# 1_AMM592.net
KiCad netlist of a schematic drawn in Altium Designer
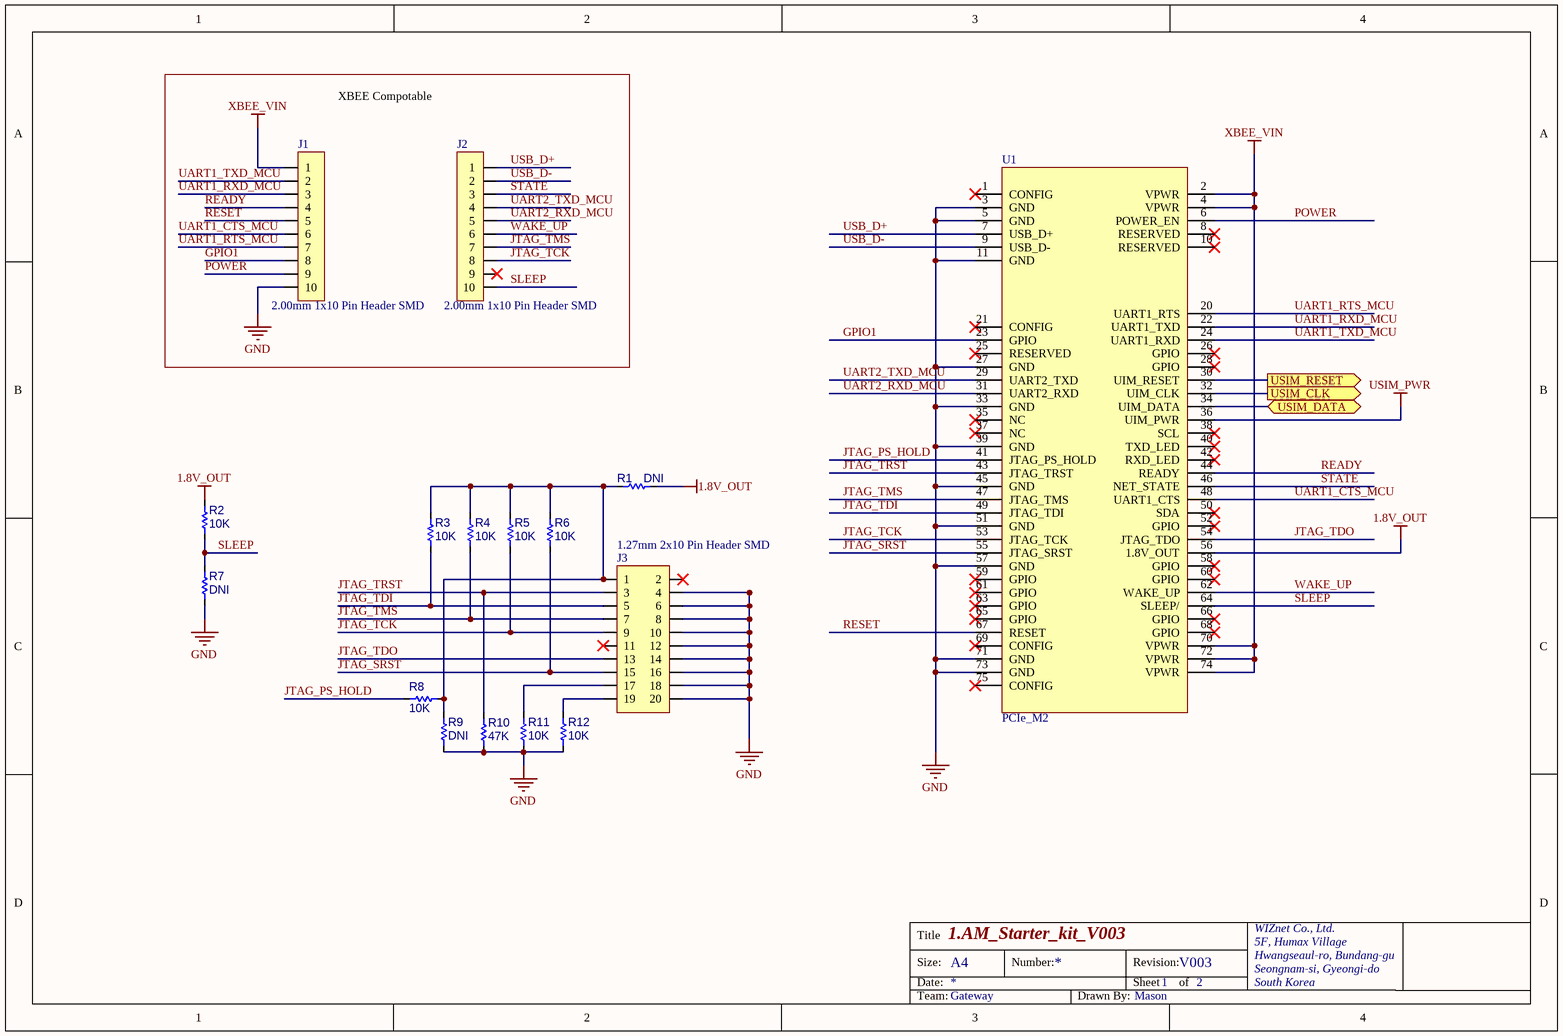
[diagram p0: 1.AMM592.SchDoc]

(export (version "E")
  (design (tool "Eeschema 10.0.6"))
  (components
    (comp (ref "J1")
      (value "2.00mm 1x10 Pin Header SMD")
      (footprint "IDC(SMD)-1X10(2MM)")
      (libsource (lib "") (part "2.00mm 1x10 Pin Header SMD_1"))
    )
    (comp (ref "J2")
      (value "2.00mm 1x10 Pin Header SMD")
      (footprint "IDC(SMD)-1X10(2MM)")
      (libsource (lib "Scott_lib") (part "2.00mm 1x10 Pin Header SMD"))
    )
    (comp (ref "J3")
      (value "1.27mm 2x10 Pin Header SMD")
      (footprint "IDC(SMD)-2X10(1.27MM)")
      (libsource (lib "Scott_lib") (part "1.27mm 2x10 Pin Header SMD"))
    )
    (comp (ref "R1")
      (value "DNI")
      (footprint "RES-0402")
      (description "RES-0402")
      (libsource (lib "Scott_lib") (part "RES-0402"))
    )
    (comp (ref "R2")
      (value "10K")
      (footprint "RES-0402")
      (description "RES-0402")
      (libsource (lib "Scott_lib") (part "RES-0402"))
    )
    (comp (ref "R3")
      (value "10K")
      (footprint "RES-0402")
      (description "RES-0402")
      (libsource (lib "Scott_lib") (part "RES-0402"))
    )
    (comp (ref "R4")
      (value "10K")
      (footprint "RES-0402")
      (description "RES-0402")
      (libsource (lib "Scott_lib") (part "RES-0402"))
    )
    (comp (ref "R5")
      (value "10K")
      (footprint "RES-0402")
      (description "RES-0402")
      (libsource (lib "Scott_lib") (part "RES-0402"))
    )
    (comp (ref "R6")
      (value "10K")
      (footprint "RES-0402")
      (description "RES-0402")
      (libsource (lib "Scott_lib") (part "RES-0402"))
    )
    (comp (ref "R7")
      (value "DNI")
      (footprint "RES-0402")
      (description "RES-0402")
      (libsource (lib "Scott_lib") (part "RES-0402"))
    )
    (comp (ref "R8")
      (value "10K")
      (footprint "RES-0402")
      (description "RES-0402")
      (libsource (lib "Scott_lib") (part "RES-0402"))
    )
    (comp (ref "R9")
      (value "DNI")
      (footprint "RES-0402")
      (description "RES-0402")
      (libsource (lib "Scott_lib") (part "RES-0402"))
    )
    (comp (ref "R10")
      (value "47K")
      (footprint "RES-0402")
      (description "RES-0402")
      (libsource (lib "Scott_lib") (part "RES-0402"))
    )
    (comp (ref "R11")
      (value "10K")
      (footprint "RES-0402")
      (description "RES-0402")
      (libsource (lib "Scott_lib") (part "RES-0402"))
    )
    (comp (ref "R12")
      (value "10K")
      (footprint "RES-0402")
      (description "RES-0402")
      (libsource (lib "Scott_lib") (part "RES-0402"))
    )
    (comp (ref "U1")
      (value "PCIe_M2")
      (footprint "PCIe_M2")
      (libsource (lib "AM_Starter_kit") (part "PCIe-M2"))
    )
  )
  (nets
    (net (code "1") (name "/GPIO1") (class "Default")
      (node (ref "J1") (pin "8") (pinfunction "8_8") (pintype "passive"))
      (node (ref "U1") (pin "23") (pinfunction "GPIO_23") (pintype "passive"))
    )
    (net (code "2") (name "/JTAG_PS_HOLD") (class "Default")
      (node (ref "R8") (pin "2") (pinfunction "2_2") (pintype "passive"))
      (node (ref "U1") (pin "41") (pinfunction "JTAG_PS_HOLD_41") (pintype "passive"))
    )
    (net (code "3") (name "/JTAG_SRST") (class "Default")
      (node (ref "J3") (pin "15") (pinfunction "15_15") (pintype "passive"))
      (node (ref "R6") (pin "1") (pinfunction "1_1") (pintype "passive"))
      (node (ref "U1") (pin "55") (pinfunction "JTAG_SRST_55") (pintype "passive"))
    )
    (net (code "4") (name "/JTAG_TCK") (class "Default")
      (node (ref "J2") (pin "8") (pinfunction "8_8") (pintype "passive"))
      (node (ref "J3") (pin "9") (pinfunction "9_9") (pintype "passive"))
      (node (ref "R5") (pin "1") (pinfunction "1_1") (pintype "passive"))
      (node (ref "U1") (pin "53") (pinfunction "JTAG_TCK_53") (pintype "passive"))
    )
    (net (code "5") (name "/JTAG_TDI") (class "Default")
      (node (ref "J3") (pin "5") (pinfunction "5_5") (pintype "passive"))
      (node (ref "R3") (pin "1") (pinfunction "1_1") (pintype "passive"))
      (node (ref "U1") (pin "49") (pinfunction "JTAG_TDI_49") (pintype "passive"))
    )
    (net (code "6") (name "/JTAG_TDO") (class "Default")
      (node (ref "J3") (pin "13") (pinfunction "13_13") (pintype "passive"))
      (node (ref "U1") (pin "54") (pinfunction "JTAG_TDO_54") (pintype "passive"))
    )
    (net (code "7") (name "/JTAG_TMS") (class "Default")
      (node (ref "J2") (pin "7") (pinfunction "7_7") (pintype "passive"))
      (node (ref "J3") (pin "7") (pinfunction "7_7") (pintype "passive"))
      (node (ref "R4") (pin "1") (pinfunction "1_1") (pintype "passive"))
      (node (ref "U1") (pin "47") (pinfunction "JTAG_TMS_47") (pintype "passive"))
    )
    (net (code "8") (name "/JTAG_TRST") (class "Default")
      (node (ref "J3") (pin "3") (pinfunction "3_3") (pintype "passive"))
      (node (ref "R10") (pin "2") (pinfunction "2_2") (pintype "passive"))
      (node (ref "U1") (pin "43") (pinfunction "JTAG_TRST_43") (pintype "passive"))
    )
    (net (code "9") (name "/POWER") (class "Default")
      (node (ref "J1") (pin "9") (pinfunction "9_9") (pintype "passive"))
      (node (ref "U1") (pin "6") (pinfunction "POWER_EN_6") (pintype "passive"))
    )
    (net (code "10") (name "/READY") (class "Default")
      (node (ref "J1") (pin "4") (pinfunction "4_4") (pintype "passive"))
      (node (ref "U1") (pin "44") (pinfunction "READY_44") (pintype "passive"))
    )
    (net (code "11") (name "/RESET") (class "Default")
      (node (ref "J1") (pin "5") (pinfunction "5_5") (pintype "passive"))
      (node (ref "U1") (pin "67") (pinfunction "RESET_67") (pintype "passive"))
    )
    (net (code "12") (name "/SLEEP") (class "Default")
      (node (ref "J2") (pin "10") (pinfunction "10_10") (pintype "passive"))
      (node (ref "R2") (pin "1") (pinfunction "1_1") (pintype "passive"))
      (node (ref "R7") (pin "2") (pinfunction "2_2") (pintype "passive"))
      (node (ref "U1") (pin "64") (pinfunction "SLEEP/_64") (pintype "passive"))
    )
    (net (code "13") (name "/STATE") (class "Default")
      (node (ref "J2") (pin "3") (pinfunction "3_3") (pintype "passive"))
      (node (ref "U1") (pin "46") (pinfunction "NET_STATE_46") (pintype "passive"))
    )
    (net (code "14") (name "/UART1_CTS_MCU") (class "Default")
      (node (ref "J1") (pin "6") (pinfunction "6_6") (pintype "passive"))
      (node (ref "U1") (pin "48") (pinfunction "UART1_CTS_48") (pintype "passive"))
    )
    (net (code "15") (name "/UART1_RTS_MCU") (class "Default")
      (node (ref "J1") (pin "7") (pinfunction "7_7") (pintype "passive"))
      (node (ref "U1") (pin "20") (pinfunction "UART1_RTS_20") (pintype "passive"))
    )
    (net (code "16") (name "/UART1_RXD_MCU") (class "Default")
      (node (ref "J1") (pin "3") (pinfunction "3_3") (pintype "passive"))
      (node (ref "U1") (pin "22") (pinfunction "UART1_TXD_22") (pintype "passive"))
    )
    (net (code "17") (name "/UART1_TXD_MCU") (class "Default")
      (node (ref "J1") (pin "2") (pinfunction "2_2") (pintype "passive"))
      (node (ref "U1") (pin "24") (pinfunction "UART1_RXD_24") (pintype "passive"))
    )
    (net (code "18") (name "/UART2_RXD_MCU") (class "Default")
      (node (ref "J2") (pin "5") (pinfunction "5_5") (pintype "passive"))
      (node (ref "U1") (pin "31") (pinfunction "UART2_RXD_31") (pintype "passive"))
    )
    (net (code "19") (name "/UART2_TXD_MCU") (class "Default")
      (node (ref "J2") (pin "4") (pinfunction "4_4") (pintype "passive"))
      (node (ref "U1") (pin "29") (pinfunction "UART2_TXD_29") (pintype "passive"))
    )
    (net (code "20") (name "/USB_D+") (class "Default")
      (node (ref "J2") (pin "1") (pinfunction "1_1") (pintype "passive"))
      (node (ref "U1") (pin "7") (pinfunction "USB_D+_7") (pintype "passive"))
    )
    (net (code "21") (name "/USB_D-") (class "Default")
      (node (ref "J2") (pin "2") (pinfunction "2_2") (pintype "passive"))
      (node (ref "U1") (pin "9") (pinfunction "USB_D-_9") (pintype "passive"))
    )
    (net (code "22") (name "/USIM_CLK") (class "Default")
      (node (ref "U1") (pin "32") (pinfunction "UIM_CLK_32") (pintype "passive"))
    )
    (net (code "23") (name "/USIM_DATA") (class "Default")
      (node (ref "U1") (pin "34") (pinfunction "UIM_DATA_34") (pintype "passive"))
    )
    (net (code "24") (name "/USIM_RESET") (class "Default")
      (node (ref "U1") (pin "30") (pinfunction "UIM_RESET_30") (pintype "passive"))
    )
    (net (code "25") (name "/WAKE_UP") (class "Default")
      (node (ref "J2") (pin "6") (pinfunction "6_6") (pintype "passive"))
      (node (ref "U1") (pin "62") (pinfunction "WAKE_UP_62") (pintype "passive"))
    )
    (net (code "26") (name "1.8V_OUT") (class "Default")
      (node (ref "R1") (pin "1") (pinfunction "1_1") (pintype "passive"))
      (node (ref "R2") (pin "2") (pinfunction "2_2") (pintype "passive"))
      (node (ref "U1") (pin "56") (pinfunction "1.8V_OUT_56") (pintype "passive"))
    )
    (net (code "27") (name "GND") (class "Default")
      (node (ref "J1") (pin "10") (pinfunction "10_10") (pintype "passive"))
      (node (ref "J3") (pin "10") (pinfunction "10_10") (pintype "passive"))
      (node (ref "J3") (pin "12") (pinfunction "12_12") (pintype "passive"))
      (node (ref "J3") (pin "14") (pinfunction "14_14") (pintype "passive"))
      (node (ref "J3") (pin "16") (pinfunction "16_16") (pintype "passive"))
      (node (ref "J3") (pin "18") (pinfunction "18_18") (pintype "passive"))
      (node (ref "J3") (pin "20") (pinfunction "20_20") (pintype "passive"))
      (node (ref "J3") (pin "4") (pinfunction "4_4") (pintype "passive"))
      (node (ref "J3") (pin "6") (pinfunction "6_6") (pintype "passive"))
      (node (ref "J3") (pin "8") (pinfunction "8_8") (pintype "passive"))
      (node (ref "R10") (pin "1") (pinfunction "1_1") (pintype "passive"))
      (node (ref "R11") (pin "1") (pinfunction "1_1") (pintype "passive"))
      (node (ref "R12") (pin "1") (pinfunction "1_1") (pintype "passive"))
      (node (ref "R7") (pin "1") (pinfunction "1_1") (pintype "passive"))
      (node (ref "R9") (pin "1") (pinfunction "1_1") (pintype "passive"))
      (node (ref "U1") (pin "11") (pinfunction "GND_11") (pintype "passive"))
      (node (ref "U1") (pin "27") (pinfunction "GND_27") (pintype "passive"))
      (node (ref "U1") (pin "3") (pinfunction "GND_3") (pintype "passive"))
      (node (ref "U1") (pin "33") (pinfunction "GND_33") (pintype "passive"))
      (node (ref "U1") (pin "39") (pinfunction "GND_39") (pintype "passive"))
      (node (ref "U1") (pin "45") (pinfunction "GND_45") (pintype "passive"))
      (node (ref "U1") (pin "5") (pinfunction "GND_5") (pintype "passive"))
      (node (ref "U1") (pin "51") (pinfunction "GND_51") (pintype "passive"))
      (node (ref "U1") (pin "57") (pinfunction "GND_57") (pintype "passive"))
      (node (ref "U1") (pin "71") (pinfunction "GND_71") (pintype "passive"))
      (node (ref "U1") (pin "73") (pinfunction "GND_73") (pintype "passive"))
    )
    (net (code "28") (name "Net-(J3-Pad1)") (class "Default")
      (node (ref "J3") (pin "1") (pinfunction "1_1") (pintype "passive"))
      (node (ref "R1") (pin "2") (pinfunction "2_2") (pintype "passive"))
      (node (ref "R3") (pin "2") (pinfunction "2_2") (pintype "passive"))
      (node (ref "R4") (pin "2") (pinfunction "2_2") (pintype "passive"))
      (node (ref "R5") (pin "2") (pinfunction "2_2") (pintype "passive"))
      (node (ref "R6") (pin "2") (pinfunction "2_2") (pintype "passive"))
      (node (ref "R8") (pin "1") (pinfunction "1_1") (pintype "passive"))
      (node (ref "R9") (pin "2") (pinfunction "2_2") (pintype "passive"))
    )
    (net (code "29") (name "Net-(J3-Pad17)") (class "Default")
      (node (ref "J3") (pin "17") (pinfunction "17_17") (pintype "passive"))
      (node (ref "R11") (pin "2") (pinfunction "2_2") (pintype "passive"))
    )
    (net (code "30") (name "Net-(J3-Pad19)") (class "Default")
      (node (ref "J3") (pin "19") (pinfunction "19_19") (pintype "passive"))
      (node (ref "R12") (pin "2") (pinfunction "2_2") (pintype "passive"))
    )
    (net (code "31") (name "USIM_PWR") (class "Default")
      (node (ref "U1") (pin "36") (pinfunction "UIM_PWR_36") (pintype "passive"))
    )
    (net (code "32") (name "XBEE_VIN") (class "Default")
      (node (ref "J1") (pin "1") (pinfunction "1_1") (pintype "passive"))
      (node (ref "U1") (pin "2") (pinfunction "VPWR_2") (pintype "passive"))
      (node (ref "U1") (pin "4") (pinfunction "VPWR_4") (pintype "passive"))
      (node (ref "U1") (pin "70") (pinfunction "VPWR_70") (pintype "passive"))
      (node (ref "U1") (pin "72") (pinfunction "VPWR_72") (pintype "passive"))
      (node (ref "U1") (pin "74") (pinfunction "VPWR_74") (pintype "passive"))
    )
    (net (code "33") (name "unconnected-(J2-Pad9)") (class "Default")
      (node (ref "J2") (pin "9") (pinfunction "9_9") (pintype "passive+no_connect"))
    )
    (net (code "34") (name "unconnected-(J3-Pad2)") (class "Default")
      (node (ref "J3") (pin "2") (pinfunction "2_2") (pintype "passive+no_connect"))
    )
    (net (code "35") (name "unconnected-(J3-Pad11)") (class "Default")
      (node (ref "J3") (pin "11") (pinfunction "11_11") (pintype "passive+no_connect"))
    )
    (net (code "36") (name "unconnected-(U1-CONFIG-Pad1)") (class "Default")
      (node (ref "U1") (pin "1") (pinfunction "CONFIG_1") (pintype "passive+no_connect"))
    )
    (net (code "37") (name "unconnected-(U1-CONFIG-Pad21)") (class "Default")
      (node (ref "U1") (pin "21") (pinfunction "CONFIG_21") (pintype "passive+no_connect"))
    )
    (net (code "38") (name "unconnected-(U1-CONFIG-Pad69)") (class "Default")
      (node (ref "U1") (pin "69") (pinfunction "CONFIG_69") (pintype "passive+no_connect"))
    )
    (net (code "39") (name "unconnected-(U1-CONFIG-Pad75)") (class "Default")
      (node (ref "U1") (pin "75") (pinfunction "CONFIG_75") (pintype "passive+no_connect"))
    )
    (net (code "40") (name "unconnected-(U1-GPIO-Pad26)") (class "Default")
      (node (ref "U1") (pin "26") (pinfunction "GPIO_26") (pintype "passive+no_connect"))
    )
    (net (code "41") (name "unconnected-(U1-GPIO-Pad28)") (class "Default")
      (node (ref "U1") (pin "28") (pinfunction "GPIO_28") (pintype "passive+no_connect"))
    )
    (net (code "42") (name "unconnected-(U1-GPIO-Pad52)") (class "Default")
      (node (ref "U1") (pin "52") (pinfunction "GPIO_52") (pintype "passive+no_connect"))
    )
    (net (code "43") (name "unconnected-(U1-GPIO-Pad58)") (class "Default")
      (node (ref "U1") (pin "58") (pinfunction "GPIO_58") (pintype "passive+no_connect"))
    )
    (net (code "44") (name "unconnected-(U1-GPIO-Pad59)") (class "Default")
      (node (ref "U1") (pin "59") (pinfunction "GPIO_59") (pintype "passive+no_connect"))
    )
    (net (code "45") (name "unconnected-(U1-GPIO-Pad60)") (class "Default")
      (node (ref "U1") (pin "60") (pinfunction "GPIO_60") (pintype "passive+no_connect"))
    )
    (net (code "46") (name "unconnected-(U1-GPIO-Pad61)") (class "Default")
      (node (ref "U1") (pin "61") (pinfunction "GPIO_61") (pintype "passive+no_connect"))
    )
    (net (code "47") (name "unconnected-(U1-GPIO-Pad63)") (class "Default")
      (node (ref "U1") (pin "63") (pinfunction "GPIO_63") (pintype "passive+no_connect"))
    )
    (net (code "48") (name "unconnected-(U1-GPIO-Pad65)") (class "Default")
      (node (ref "U1") (pin "65") (pinfunction "GPIO_65") (pintype "passive+no_connect"))
    )
    (net (code "49") (name "unconnected-(U1-GPIO-Pad66)") (class "Default")
      (node (ref "U1") (pin "66") (pinfunction "GPIO_66") (pintype "passive+no_connect"))
    )
    (net (code "50") (name "unconnected-(U1-GPIO-Pad68)") (class "Default")
      (node (ref "U1") (pin "68") (pinfunction "GPIO_68") (pintype "passive+no_connect"))
    )
    (net (code "51") (name "unconnected-(U1-NC-Pad35)") (class "Default")
      (node (ref "U1") (pin "35") (pinfunction "NC_35") (pintype "passive+no_connect"))
    )
    (net (code "52") (name "unconnected-(U1-NC-Pad37)") (class "Default")
      (node (ref "U1") (pin "37") (pinfunction "NC_37") (pintype "passive+no_connect"))
    )
    (net (code "53") (name "unconnected-(U1-RESERVED-Pad8)") (class "Default")
      (node (ref "U1") (pin "8") (pinfunction "RESERVED_8") (pintype "passive+no_connect"))
    )
    (net (code "54") (name "unconnected-(U1-RESERVED-Pad10)") (class "Default")
      (node (ref "U1") (pin "10") (pinfunction "RESERVED_10") (pintype "passive+no_connect"))
    )
    (net (code "55") (name "unconnected-(U1-RESERVED-Pad25)") (class "Default")
      (node (ref "U1") (pin "25") (pinfunction "RESERVED_25") (pintype "passive+no_connect"))
    )
    (net (code "56") (name "unconnected-(U1-RXD_LED-Pad42)") (class "Default")
      (node (ref "U1") (pin "42") (pinfunction "RXD_LED_42") (pintype "passive+no_connect"))
    )
    (net (code "57") (name "unconnected-(U1-SCL-Pad38)") (class "Default")
      (node (ref "U1") (pin "38") (pinfunction "SCL_38") (pintype "passive+no_connect"))
    )
    (net (code "58") (name "unconnected-(U1-SDA-Pad50)") (class "Default")
      (node (ref "U1") (pin "50") (pinfunction "SDA_50") (pintype "passive+no_connect"))
    )
    (net (code "59") (name "unconnected-(U1-TXD_LED-Pad40)") (class "Default")
      (node (ref "U1") (pin "40") (pinfunction "TXD_LED_40") (pintype "passive+no_connect"))
    )
  )
)
